# PanelBoard.net
KiCad netlist of a schematic drawn in EAGLE
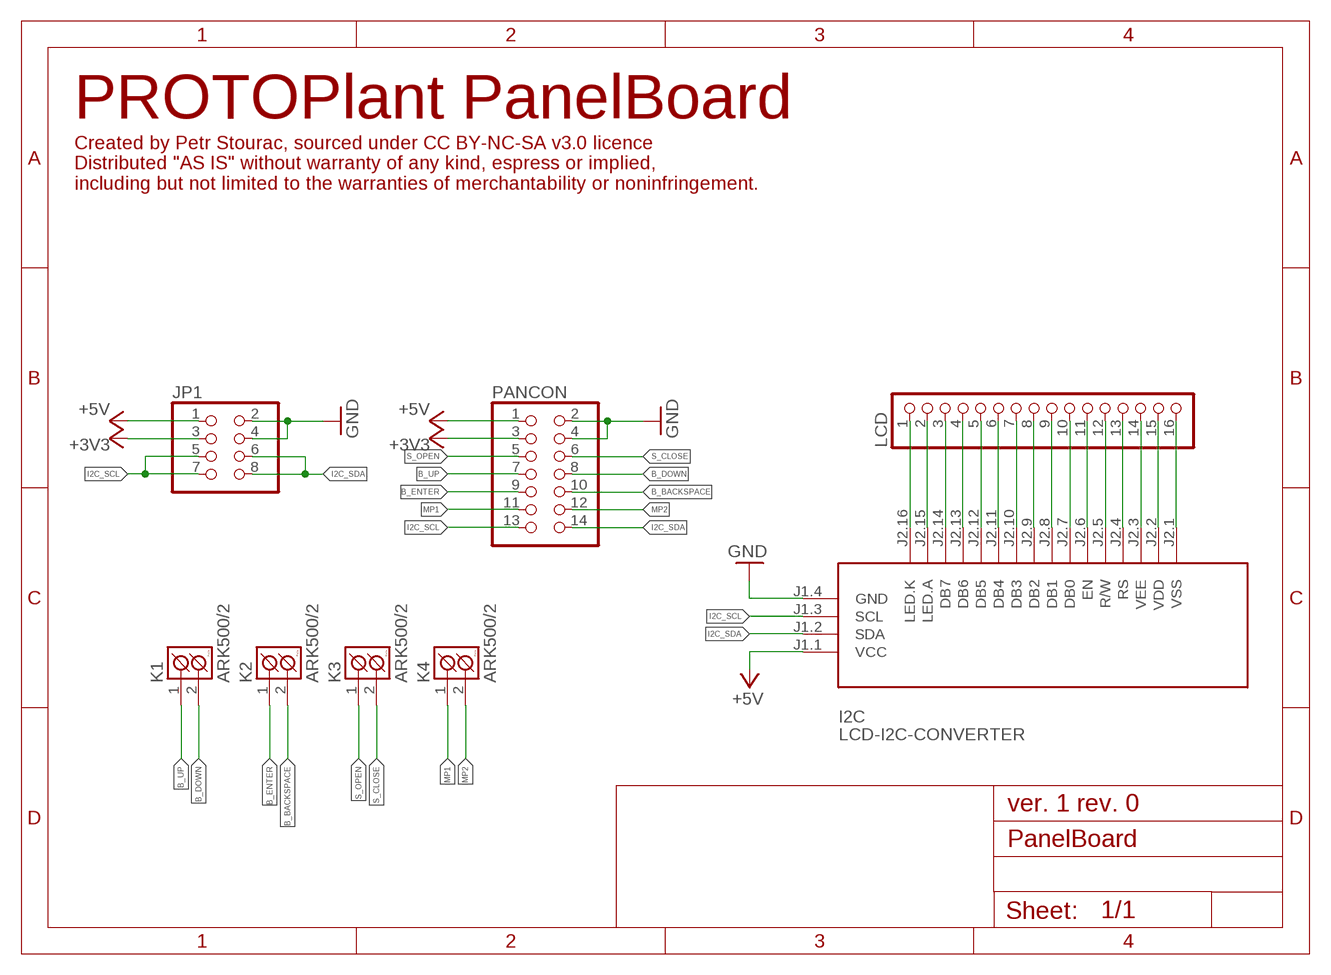
[diagram p0: schematic, sheet 1]

(export (version "E")
  (design (tool "Eeschema 10.0.6"))
  (components
    (comp (ref "I2C")
      (value "LCD-I2C-CONVERTER")
      (footprint "eagle-import:LCD-I2C-CONVERTER")
      (libsource (lib "eagle-import") (part "LCD-I2C-CONVERTER"))
    )
    (comp (ref "JP1")
      (value "PINHD-2X4/90")
      (footprint "eagle-import:2X04_90")
      (libsource (lib "eagle-import") (part "PINHD-2X4/90"))
    )
    (comp (ref "K1")
      (value "ARK500/2")
      (footprint "eagle-import:ARK500_2")
      (libsource (lib "eagle-import") (part "ARK500/2"))
    )
    (comp (ref "K2")
      (value "ARK500/2")
      (footprint "eagle-import:ARK500_2")
      (libsource (lib "eagle-import") (part "ARK500/2"))
    )
    (comp (ref "K3")
      (value "ARK500/2")
      (footprint "eagle-import:ARK500_2")
      (libsource (lib "eagle-import") (part "ARK500/2"))
    )
    (comp (ref "K4")
      (value "ARK500/2")
      (footprint "eagle-import:ARK500_2")
      (libsource (lib "eagle-import") (part "ARK500/2"))
    )
    (comp (ref "LCD")
      (value "PINHD-1X16")
      (footprint "eagle-import:1X16")
      (libsource (lib "eagle-import") (part "PINHD-1X16"))
    )
    (comp (ref "PANCON")
      (value "PINHD-2X7/90")
      (footprint "eagle-import:2X07_90")
      (libsource (lib "eagle-import") (part "PINHD-2X7/90"))
    )
  )
  (nets
    (net (code "1") (name "+3V3") (class "Default")
      (node (ref "JP1") (pin "3") (pinfunction "3_3") (pintype "passive"))
      (node (ref "PANCON") (pin "3") (pinfunction "3_3") (pintype "passive"))
    )
    (net (code "2") (name "+5V") (class "Default")
      (node (ref "I2C") (pin "J1.1") (pinfunction "VCC_J1.1") (pintype "power_in"))
      (node (ref "JP1") (pin "1") (pinfunction "1_1") (pintype "passive"))
      (node (ref "PANCON") (pin "1") (pinfunction "1_1") (pintype "passive"))
    )
    (net (code "3") (name "B_BACKSPACE") (class "Default")
      (node (ref "K2") (pin "2") (pinfunction "K2_2") (pintype "passive"))
      (node (ref "PANCON") (pin "10") (pinfunction "10_10") (pintype "passive"))
    )
    (net (code "4") (name "B_DOWN") (class "Default")
      (node (ref "K1") (pin "2") (pinfunction "K2_2") (pintype "passive"))
      (node (ref "PANCON") (pin "8") (pinfunction "8_8") (pintype "passive"))
    )
    (net (code "5") (name "B_ENTER") (class "Default")
      (node (ref "K2") (pin "1") (pinfunction "K1_1") (pintype "passive"))
      (node (ref "PANCON") (pin "9") (pinfunction "9_9") (pintype "passive"))
    )
    (net (code "6") (name "B_UP") (class "Default")
      (node (ref "K1") (pin "1") (pinfunction "K1_1") (pintype "passive"))
      (node (ref "PANCON") (pin "7") (pinfunction "7_7") (pintype "passive"))
    )
    (net (code "7") (name "GND") (class "Default")
      (node (ref "I2C") (pin "J1.4") (pinfunction "GND_J1.4") (pintype "power_in"))
      (node (ref "JP1") (pin "2") (pinfunction "2_2") (pintype "passive"))
      (node (ref "JP1") (pin "4") (pinfunction "4_4") (pintype "passive"))
      (node (ref "PANCON") (pin "2") (pinfunction "2_2") (pintype "passive"))
      (node (ref "PANCON") (pin "4") (pinfunction "4_4") (pintype "passive"))
    )
    (net (code "8") (name "I2C_SCL") (class "Default")
      (node (ref "I2C") (pin "J1.3") (pinfunction "SCL_J1.3") (pintype "bidirectional"))
      (node (ref "JP1") (pin "5") (pinfunction "5_5") (pintype "passive"))
      (node (ref "JP1") (pin "7") (pinfunction "7_7") (pintype "passive"))
      (node (ref "PANCON") (pin "13") (pinfunction "13_13") (pintype "passive"))
    )
    (net (code "9") (name "I2C_SDA") (class "Default")
      (node (ref "I2C") (pin "J1.2") (pinfunction "SDA_J1.2") (pintype "bidirectional"))
      (node (ref "JP1") (pin "6") (pinfunction "6_6") (pintype "passive"))
      (node (ref "JP1") (pin "8") (pinfunction "8_8") (pintype "passive"))
      (node (ref "PANCON") (pin "14") (pinfunction "14_14") (pintype "passive"))
    )
    (net (code "10") (name "MP1") (class "Default")
      (node (ref "K4") (pin "1") (pinfunction "K1_1") (pintype "passive"))
      (node (ref "PANCON") (pin "11") (pinfunction "11_11") (pintype "passive"))
    )
    (net (code "11") (name "MP2") (class "Default")
      (node (ref "K4") (pin "2") (pinfunction "K2_2") (pintype "passive"))
      (node (ref "PANCON") (pin "12") (pinfunction "12_12") (pintype "passive"))
    )
    (net (code "12") (name "Net-(I2C-DB0)") (class "Default")
      (node (ref "I2C") (pin "J2.7") (pinfunction "DB0_J2.7") (pintype "bidirectional"))
      (node (ref "LCD") (pin "10") (pinfunction "10_10") (pintype "passive"))
    )
    (net (code "13") (name "Net-(I2C-DB1)") (class "Default")
      (node (ref "I2C") (pin "J2.8") (pinfunction "DB1_J2.8") (pintype "bidirectional"))
      (node (ref "LCD") (pin "9") (pinfunction "9_9") (pintype "passive"))
    )
    (net (code "14") (name "Net-(I2C-DB2)") (class "Default")
      (node (ref "I2C") (pin "J2.9") (pinfunction "DB2_J2.9") (pintype "bidirectional"))
      (node (ref "LCD") (pin "8") (pinfunction "8_8") (pintype "passive"))
    )
    (net (code "15") (name "Net-(I2C-DB3)") (class "Default")
      (node (ref "I2C") (pin "J2.10") (pinfunction "DB3_J2.10") (pintype "bidirectional"))
      (node (ref "LCD") (pin "7") (pinfunction "7_7") (pintype "passive"))
    )
    (net (code "16") (name "Net-(I2C-DB4)") (class "Default")
      (node (ref "I2C") (pin "J2.11") (pinfunction "DB4_J2.11") (pintype "bidirectional"))
      (node (ref "LCD") (pin "6") (pinfunction "6_6") (pintype "passive"))
    )
    (net (code "17") (name "Net-(I2C-DB5)") (class "Default")
      (node (ref "I2C") (pin "J2.12") (pinfunction "DB5_J2.12") (pintype "bidirectional"))
      (node (ref "LCD") (pin "5") (pinfunction "5_5") (pintype "passive"))
    )
    (net (code "18") (name "Net-(I2C-DB6)") (class "Default")
      (node (ref "I2C") (pin "J2.13") (pinfunction "DB6_J2.13") (pintype "bidirectional"))
      (node (ref "LCD") (pin "4") (pinfunction "4_4") (pintype "passive"))
    )
    (net (code "19") (name "Net-(I2C-DB7)") (class "Default")
      (node (ref "I2C") (pin "J2.14") (pinfunction "DB7_J2.14") (pintype "bidirectional"))
      (node (ref "LCD") (pin "3") (pinfunction "3_3") (pintype "passive"))
    )
    (net (code "20") (name "Net-(I2C-EN)") (class "Default")
      (node (ref "I2C") (pin "J2.6") (pinfunction "EN_J2.6") (pintype "bidirectional"))
      (node (ref "LCD") (pin "11") (pinfunction "11_11") (pintype "passive"))
    )
    (net (code "21") (name "Net-(I2C-LED.A)") (class "Default")
      (node (ref "I2C") (pin "J2.15") (pinfunction "LED.A_J2.15") (pintype "bidirectional"))
      (node (ref "LCD") (pin "2") (pinfunction "2_2") (pintype "passive"))
    )
    (net (code "22") (name "Net-(I2C-LED.K)") (class "Default")
      (node (ref "I2C") (pin "J2.16") (pinfunction "LED.K_J2.16") (pintype "bidirectional"))
      (node (ref "LCD") (pin "1") (pinfunction "1_1") (pintype "passive"))
    )
    (net (code "23") (name "Net-(I2C-RS)") (class "Default")
      (node (ref "I2C") (pin "J2.4") (pinfunction "RS_J2.4") (pintype "bidirectional"))
      (node (ref "LCD") (pin "13") (pinfunction "13_13") (pintype "passive"))
    )
    (net (code "24") (name "Net-(I2C-R{slash}W)") (class "Default")
      (node (ref "I2C") (pin "J2.5") (pinfunction "R/W_J2.5") (pintype "bidirectional"))
      (node (ref "LCD") (pin "12") (pinfunction "12_12") (pintype "passive"))
    )
    (net (code "25") (name "Net-(I2C-VDD)") (class "Default")
      (node (ref "I2C") (pin "J2.2") (pinfunction "VDD_J2.2") (pintype "bidirectional"))
      (node (ref "LCD") (pin "15") (pinfunction "15_15") (pintype "passive"))
    )
    (net (code "26") (name "Net-(I2C-VEE)") (class "Default")
      (node (ref "I2C") (pin "J2.3") (pinfunction "VEE_J2.3") (pintype "bidirectional"))
      (node (ref "LCD") (pin "14") (pinfunction "14_14") (pintype "passive"))
    )
    (net (code "27") (name "Net-(I2C-VSS)") (class "Default")
      (node (ref "I2C") (pin "J2.1") (pinfunction "VSS_J2.1") (pintype "bidirectional"))
      (node (ref "LCD") (pin "16") (pinfunction "16_16") (pintype "passive"))
    )
    (net (code "28") (name "S_CLOSE") (class "Default")
      (node (ref "K3") (pin "2") (pinfunction "K2_2") (pintype "passive"))
      (node (ref "PANCON") (pin "6") (pinfunction "6_6") (pintype "passive"))
    )
    (net (code "29") (name "S_OPEN") (class "Default")
      (node (ref "K3") (pin "1") (pinfunction "K1_1") (pintype "passive"))
      (node (ref "PANCON") (pin "5") (pinfunction "5_5") (pintype "passive"))
    )
  )
)
